# blank_rev_2.net
KiCad netlist of a schematic drawn in EAGLE
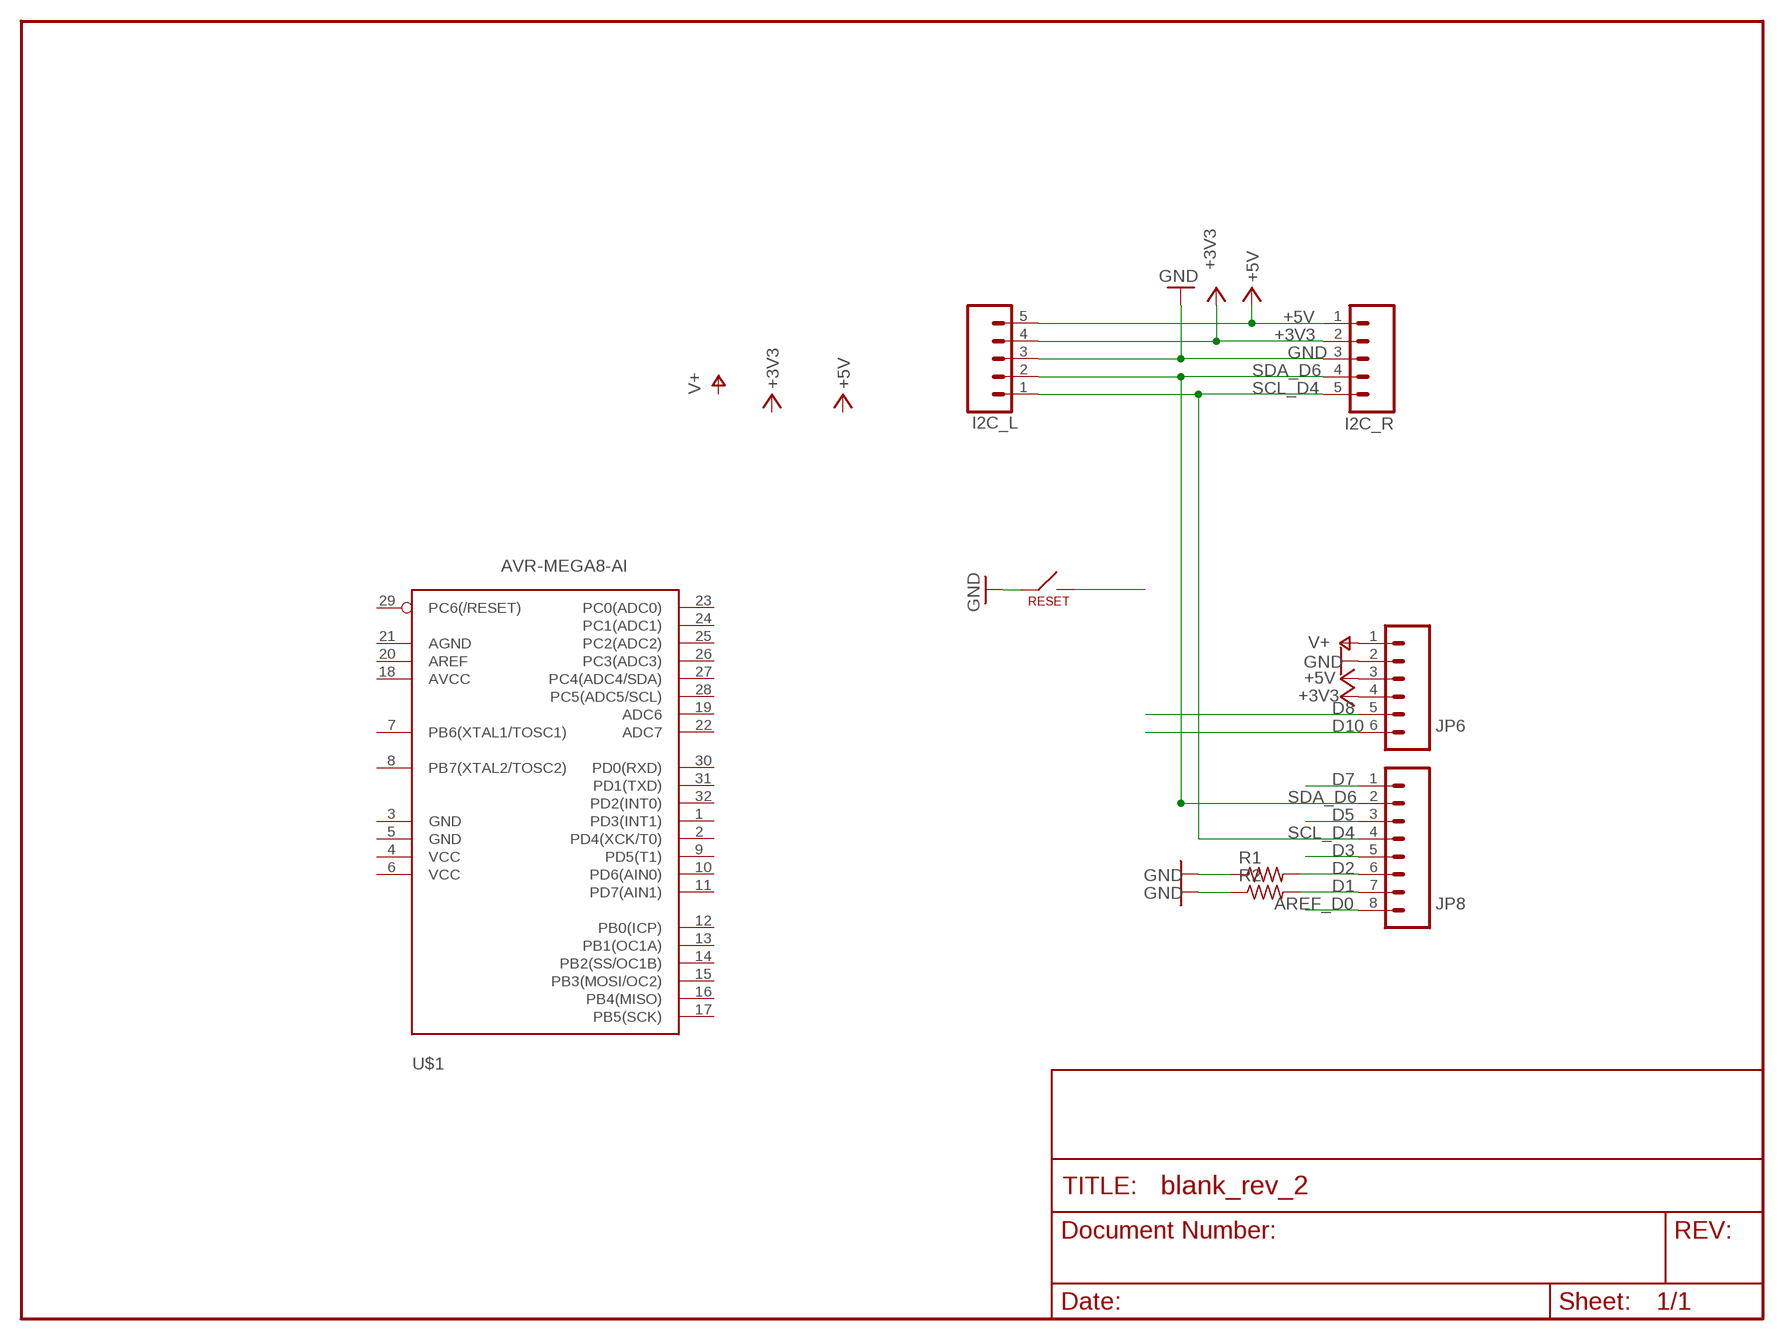
[diagram p0: schematic, sheet 1]

(export (version "E")
  (design (tool "Eeschema 10.0.6"))
  (components
    (comp (ref "I2C_L")
      (value "M05PTH")
      (footprint "eagle-import:1X05")
      (libsource (lib "eagle-import") (part "M05PTH"))
    )
    (comp (ref "I2C_R")
      (value "M05PTH")
      (footprint "eagle-import:1X05")
      (libsource (lib "eagle-import") (part "M05PTH"))
    )
    (comp (ref "JP6")
      (value "M06SIP")
      (footprint "eagle-import:1X06")
      (libsource (lib "eagle-import") (part "M06SIP"))
    )
    (comp (ref "JP8")
      (value "M081X08")
      (footprint "eagle-import:1X08")
      (libsource (lib "eagle-import") (part "M081X08"))
    )
    (comp (ref "R1")
      (value "R-US_0204/2V")
      (footprint "eagle-import:0204V")
      (libsource (lib "eagle-import") (part "R-US_0204/2V"))
    )
    (comp (ref "R2")
      (value "R-US_0204/2V")
      (footprint "eagle-import:0204V")
      (libsource (lib "eagle-import") (part "R-US_0204/2V"))
    )
    (comp (ref "RESET")
      (value "PTS635_SWITCH")
      (footprint "eagle-import:PTS635_SWITCH")
      (libsource (lib "eagle-import") (part "PTS635_SWITCH"))
    )
    (comp (ref "U$1")
      (value "AVR-MEGA8-AI")
      (footprint "eagle-import:TQFP32-08")
      (libsource (lib "eagle-import") (part "AVR-MEGA8-AI"))
    )
  )
  (nets
    (net (code "1") (name "+3V3") (class "Default")
      (node (ref "I2C_L") (pin "4") (pinfunction "4_4") (pintype "passive"))
      (node (ref "I2C_R") (pin "2") (pinfunction "2_2") (pintype "passive"))
      (node (ref "JP6") (pin "4") (pinfunction "4_4") (pintype "passive"))
    )
    (net (code "2") (name "+5V") (class "Default")
      (node (ref "I2C_L") (pin "5") (pinfunction "5_5") (pintype "passive"))
      (node (ref "I2C_R") (pin "1") (pinfunction "1_1") (pintype "passive"))
      (node (ref "JP6") (pin "3") (pinfunction "3_3") (pintype "passive"))
    )
    (net (code "3") (name "/AREF_D0") (class "Default")
      (node (ref "JP8") (pin "8") (pinfunction "8_8") (pintype "passive"))
    )
    (net (code "4") (name "/D1") (class "Default")
      (node (ref "JP8") (pin "7") (pinfunction "7_7") (pintype "passive"))
      (node (ref "R2") (pin "2") (pinfunction "2_2") (pintype "passive"))
    )
    (net (code "5") (name "/D2") (class "Default")
      (node (ref "JP8") (pin "6") (pinfunction "6_6") (pintype "passive"))
      (node (ref "R1") (pin "2") (pinfunction "2_2") (pintype "passive"))
    )
    (net (code "6") (name "/D3") (class "Default")
      (node (ref "JP8") (pin "5") (pinfunction "5_5") (pintype "passive"))
    )
    (net (code "7") (name "/D5") (class "Default")
      (node (ref "JP8") (pin "3") (pinfunction "3_3") (pintype "passive"))
    )
    (net (code "8") (name "/D7") (class "Default")
      (node (ref "JP8") (pin "1") (pinfunction "1_1") (pintype "passive"))
    )
    (net (code "9") (name "/D8") (class "Default")
      (node (ref "JP6") (pin "5") (pinfunction "5_5") (pintype "passive"))
    )
    (net (code "10") (name "/D10") (class "Default")
      (node (ref "JP6") (pin "6") (pinfunction "6_6") (pintype "passive"))
    )
    (net (code "11") (name "/SCL_D4") (class "Default")
      (node (ref "I2C_L") (pin "1") (pinfunction "1_1") (pintype "passive"))
      (node (ref "I2C_R") (pin "5") (pinfunction "5_5") (pintype "passive"))
      (node (ref "JP8") (pin "4") (pinfunction "4_4") (pintype "passive"))
    )
    (net (code "12") (name "/SDA_D6") (class "Default")
      (node (ref "I2C_L") (pin "2") (pinfunction "2_2") (pintype "passive"))
      (node (ref "I2C_R") (pin "4") (pinfunction "4_4") (pintype "passive"))
      (node (ref "JP8") (pin "2") (pinfunction "2_2") (pintype "passive"))
    )
    (net (code "13") (name "GND") (class "Default")
      (node (ref "I2C_L") (pin "3") (pinfunction "3_3") (pintype "passive"))
      (node (ref "I2C_R") (pin "3") (pinfunction "3_3") (pintype "passive"))
      (node (ref "JP6") (pin "2") (pinfunction "2_2") (pintype "passive"))
      (node (ref "R1") (pin "1") (pinfunction "1_1") (pintype "passive"))
      (node (ref "R2") (pin "1") (pinfunction "1_1") (pintype "passive"))
      (node (ref "RESET") (pin "P$1") (pinfunction "P$1_P$1") (pintype "bidirectional"))
    )
    (net (code "14") (name "V+") (class "Default")
      (node (ref "JP6") (pin "1") (pinfunction "1_1") (pintype "passive"))
    )
    (net (code "15") (name "unconnected-(RESET-PadP$2)") (class "Default")
      (node (ref "RESET") (pin "P$2") (pinfunction "P$2_P$2") (pintype "bidirectional"))
    )
    (net (code "16") (name "unconnected-(U$1-ADC6-Pad19)") (class "Default")
      (node (ref "U$1") (pin "19") (pinfunction "ADC6_19") (pintype "bidirectional"))
    )
    (net (code "17") (name "unconnected-(U$1-ADC7-Pad22)") (class "Default")
      (node (ref "U$1") (pin "22") (pinfunction "ADC7_22") (pintype "bidirectional"))
    )
    (net (code "18") (name "unconnected-(U$1-AGND-Pad21)") (class "Default")
      (node (ref "U$1") (pin "21") (pinfunction "AGND_21") (pintype "bidirectional"))
    )
    (net (code "19") (name "unconnected-(U$1-AREF-Pad20)") (class "Default")
      (node (ref "U$1") (pin "20") (pinfunction "AREF_20") (pintype "bidirectional"))
    )
    (net (code "20") (name "unconnected-(U$1-AVCC-Pad18)") (class "Default")
      (node (ref "U$1") (pin "18") (pinfunction "AVCC_18") (pintype "bidirectional"))
    )
    (net (code "21") (name "unconnected-(U$1-GND-Pad3)") (class "Default")
      (node (ref "U$1") (pin "3") (pinfunction "GND_3") (pintype "bidirectional"))
    )
    (net (code "22") (name "unconnected-(U$1-GND-Pad5)") (class "Default")
      (node (ref "U$1") (pin "5") (pinfunction "GND_5") (pintype "bidirectional"))
    )
    (net (code "23") (name "unconnected-(U$1-PB0(ICP)-Pad12)") (class "Default")
      (node (ref "U$1") (pin "12") (pinfunction "PB0(ICP)_12") (pintype "bidirectional"))
    )
    (net (code "24") (name "unconnected-(U$1-PB1(OC1A)-Pad13)") (class "Default")
      (node (ref "U$1") (pin "13") (pinfunction "PB1(OC1A)_13") (pintype "bidirectional"))
    )
    (net (code "25") (name "unconnected-(U$1-PB2(SS{slash}OC1B)-Pad14)") (class "Default")
      (node (ref "U$1") (pin "14") (pinfunction "PB2(SS/OC1B)_14") (pintype "bidirectional"))
    )
    (net (code "26") (name "unconnected-(U$1-PB3(MOSI{slash}OC2)-Pad15)") (class "Default")
      (node (ref "U$1") (pin "15") (pinfunction "PB3(MOSI/OC2)_15") (pintype "bidirectional"))
    )
    (net (code "27") (name "unconnected-(U$1-PB4(MISO)-Pad16)") (class "Default")
      (node (ref "U$1") (pin "16") (pinfunction "PB4(MISO)_16") (pintype "bidirectional"))
    )
    (net (code "28") (name "unconnected-(U$1-PB5(SCK)-Pad17)") (class "Default")
      (node (ref "U$1") (pin "17") (pinfunction "PB5(SCK)_17") (pintype "bidirectional"))
    )
    (net (code "29") (name "unconnected-(U$1-PB6(XTAL1{slash}TOSC1)-Pad7)") (class "Default")
      (node (ref "U$1") (pin "7") (pinfunction "PB6(XTAL1/TOSC1)_7") (pintype "bidirectional"))
    )
    (net (code "30") (name "unconnected-(U$1-PB7(XTAL2{slash}TOSC2)-Pad8)") (class "Default")
      (node (ref "U$1") (pin "8") (pinfunction "PB7(XTAL2/TOSC2)_8") (pintype "bidirectional"))
    )
    (net (code "31") (name "unconnected-(U$1-PC0(ADC0)-Pad23)") (class "Default")
      (node (ref "U$1") (pin "23") (pinfunction "PC0(ADC0)_23") (pintype "bidirectional"))
    )
    (net (code "32") (name "unconnected-(U$1-PC1(ADC1)-Pad24)") (class "Default")
      (node (ref "U$1") (pin "24") (pinfunction "PC1(ADC1)_24") (pintype "bidirectional"))
    )
    (net (code "33") (name "unconnected-(U$1-PC2(ADC2)-Pad25)") (class "Default")
      (node (ref "U$1") (pin "25") (pinfunction "PC2(ADC2)_25") (pintype "bidirectional"))
    )
    (net (code "34") (name "unconnected-(U$1-PC3(ADC3)-Pad26)") (class "Default")
      (node (ref "U$1") (pin "26") (pinfunction "PC3(ADC3)_26") (pintype "bidirectional"))
    )
    (net (code "35") (name "unconnected-(U$1-PC4(ADC4{slash}SDA)-Pad27)") (class "Default")
      (node (ref "U$1") (pin "27") (pinfunction "PC4(ADC4/SDA)_27") (pintype "bidirectional"))
    )
    (net (code "36") (name "unconnected-(U$1-PC5(ADC5{slash}SCL)-Pad28)") (class "Default")
      (node (ref "U$1") (pin "28") (pinfunction "PC5(ADC5/SCL)_28") (pintype "bidirectional"))
    )
    (net (code "37") (name "unconnected-(U$1-PC6({slash}RESET)-Pad29)") (class "Default")
      (node (ref "U$1") (pin "29") (pinfunction "PC6(/RESET)_29") (pintype "bidirectional"))
    )
    (net (code "38") (name "unconnected-(U$1-PD0(RXD)-Pad30)") (class "Default")
      (node (ref "U$1") (pin "30") (pinfunction "PD0(RXD)_30") (pintype "bidirectional"))
    )
    (net (code "39") (name "unconnected-(U$1-PD1(TXD)-Pad31)") (class "Default")
      (node (ref "U$1") (pin "31") (pinfunction "PD1(TXD)_31") (pintype "bidirectional"))
    )
    (net (code "40") (name "unconnected-(U$1-PD2(INT0)-Pad32)") (class "Default")
      (node (ref "U$1") (pin "32") (pinfunction "PD2(INT0)_32") (pintype "bidirectional"))
    )
    (net (code "41") (name "unconnected-(U$1-PD3(INT1)-Pad1)") (class "Default")
      (node (ref "U$1") (pin "1") (pinfunction "PD3(INT1)_1") (pintype "bidirectional"))
    )
    (net (code "42") (name "unconnected-(U$1-PD4(XCK{slash}T0)-Pad2)") (class "Default")
      (node (ref "U$1") (pin "2") (pinfunction "PD4(XCK/T0)_2") (pintype "bidirectional"))
    )
    (net (code "43") (name "unconnected-(U$1-PD5(T1)-Pad9)") (class "Default")
      (node (ref "U$1") (pin "9") (pinfunction "PD5(T1)_9") (pintype "bidirectional"))
    )
    (net (code "44") (name "unconnected-(U$1-PD6(AIN0)-Pad10)") (class "Default")
      (node (ref "U$1") (pin "10") (pinfunction "PD6(AIN0)_10") (pintype "bidirectional"))
    )
    (net (code "45") (name "unconnected-(U$1-PD7(AIN1)-Pad11)") (class "Default")
      (node (ref "U$1") (pin "11") (pinfunction "PD7(AIN1)_11") (pintype "bidirectional"))
    )
    (net (code "46") (name "unconnected-(U$1-VCC-Pad4)") (class "Default")
      (node (ref "U$1") (pin "4") (pinfunction "VCC_4") (pintype "bidirectional"))
    )
    (net (code "47") (name "unconnected-(U$1-VCC-Pad6)") (class "Default")
      (node (ref "U$1") (pin "6") (pinfunction "VCC_6") (pintype "bidirectional"))
    )
  )
)
